# Control-Board-V3-Charging_v21.net
KiCad netlist of a schematic drawn in EAGLE
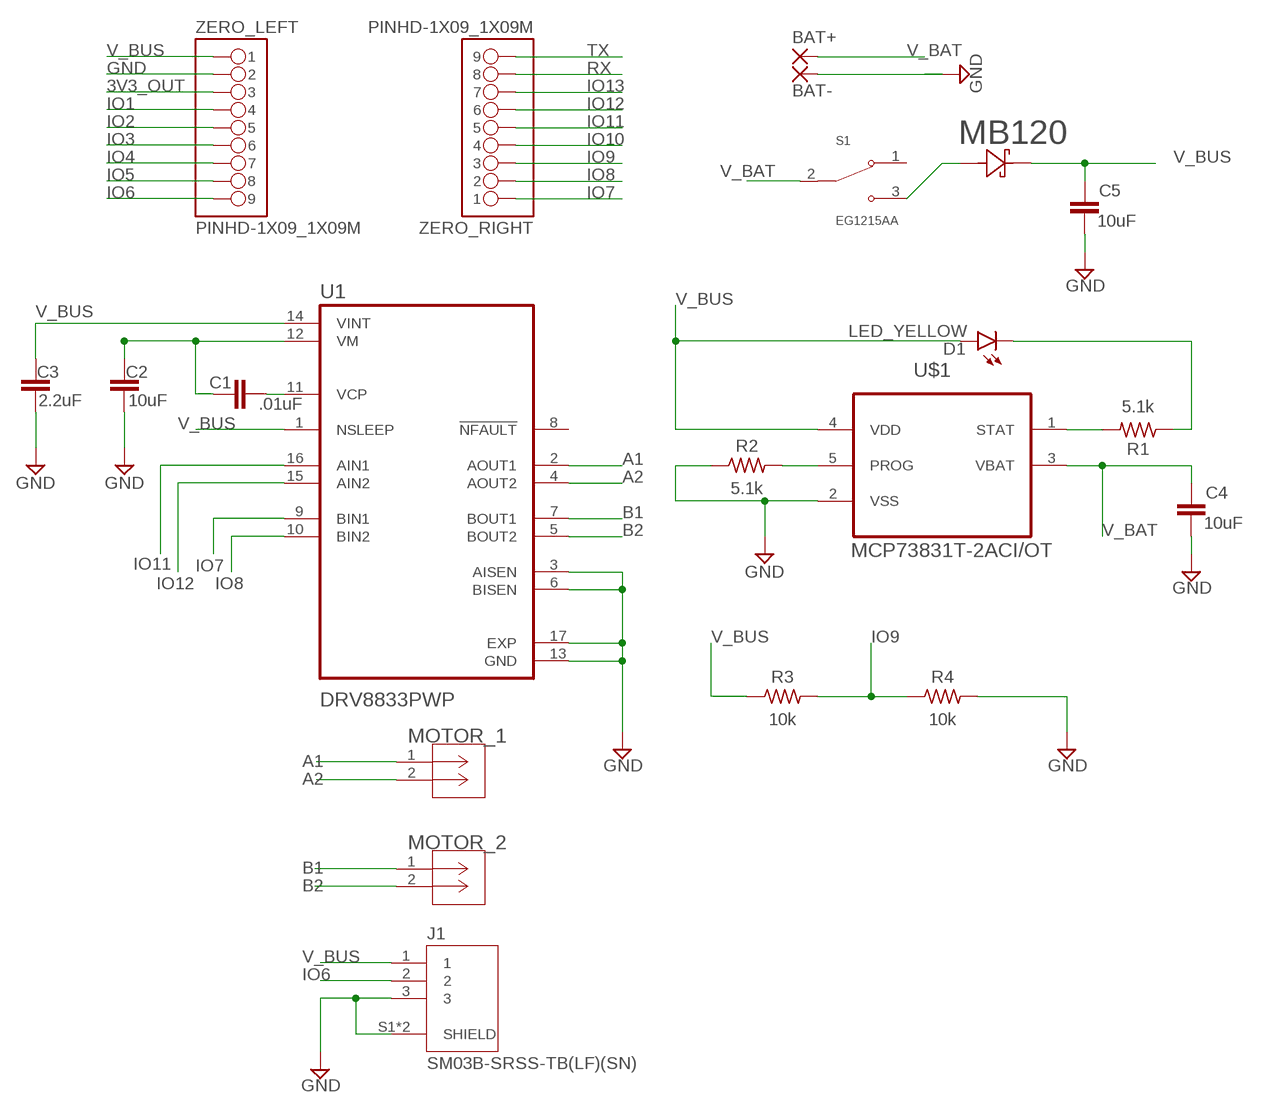
[diagram p0: schematic, sheet 1]

(export (version "E")
  (design (tool "Eeschema 10.0.6"))
  (components
    (comp (ref "BAT+")
      (value "SMD2")
      (footprint "eagle-import:SMD1,27-2,54")
      (libsource (lib "eagle-import") (part "SMD2"))
    )
    (comp (ref "BAT-")
      (value "SMD2")
      (footprint "eagle-import:SMD1,27-2,54")
      (libsource (lib "eagle-import") (part "SMD2"))
    )
    (comp (ref "C1")
      (value ".01uF")
      (footprint "eagle-import:CAPC2012X110")
      (libsource (lib "eagle-import") (part "CCHIP-0805(2012-METRIC)_"))
    )
    (comp (ref "C2")
      (value "10uF")
      (footprint "eagle-import:CAPC2012X110")
      (libsource (lib "eagle-import") (part "CCHIP-0805(2012-METRIC)_"))
    )
    (comp (ref "C3")
      (value "2.2uF")
      (footprint "eagle-import:CAPC2012X110")
      (libsource (lib "eagle-import") (part "CCHIP-0805(2012-METRIC)_"))
    )
    (comp (ref "C4")
      (value "10uF")
      (footprint "eagle-import:CAPC2012X110")
      (libsource (lib "eagle-import") (part "Capacitor_16290819_CCHIP-0805(2012-METRIC)_"))
    )
    (comp (ref "C5")
      (value "10uF")
      (footprint "eagle-import:CAPC2012X110")
      (libsource (lib "eagle-import") (part "Capacitor_16290819_CCHIP-0805(2012-METRIC)_"))
    )
    (comp (ref "D1")
      (value "LED_YELLOW")
      (footprint "eagle-import:LEDC2012X110N_FLAT-Y")
      (libsource (lib "eagle-import") (part "CHIP-FLAT-Y_0805"))
    )
    (comp (ref "J1")
      (value "SM03B-SRSS-TB(LF)(SN)")
      (footprint "eagle-import:JST_SM03B-SRSS-TB(LF)(SN)")
      (fields (field (name "MF") "JST Sales America Inc."))
      (libsource (lib "eagle-import") (part "SM03B-SRSS-TB(LF)(SN)"))
    )
    (comp (ref "MB120")
      (value "MBR120LSFT3GSDO_SOD-123FL(498)_OSI-L")
      (footprint "eagle-import:SDO_SOD-123FL(498)_OSI-L")
      (fields
        (field (name "MANUFACTURER_PART_NUMBER") "MBR120LSFT3G")
        (field (name "COPYRIGHT") "Copyright (C) 2024 Ultra Librarian. All rights reserved.")
      )
      (libsource (lib "eagle-import") (part "MBR120LSFT3GSDO_SOD-123FL(498)_OSI-L"))
    )
    (comp (ref "MOTOR_1")
      (value "JST_SH")
      (footprint "eagle-import:JST")
      (libsource (lib "eagle-import") (part "JST_SH"))
    )
    (comp (ref "MOTOR_2")
      (value "JST_SH")
      (footprint "eagle-import:JST")
      (libsource (lib "eagle-import") (part "JST_SH"))
    )
    (comp (ref "R1")
      (value "5.1k")
      (footprint "eagle-import:RESC2012X65")
      (libsource (lib "eagle-import") (part "R-USCHIP-0805(2012-METRIC)_"))
    )
    (comp (ref "R2")
      (value "5.1k")
      (footprint "eagle-import:RESC2012X65")
      (libsource (lib "eagle-import") (part "R-USCHIP-0805(2012-METRIC)_"))
    )
    (comp (ref "R3")
      (value "10k")
      (footprint "eagle-import:RESC2012X65")
      (libsource (lib "eagle-import") (part "R-USCHIP-0805(2012-METRIC)_"))
    )
    (comp (ref "R4")
      (value "10k")
      (footprint "eagle-import:RESC2012X65")
      (libsource (lib "eagle-import") (part "R-USCHIP-0805(2012-METRIC)_"))
    )
    (comp (ref "S1")
      (value "EG1215AA")
      (footprint "eagle-import:SW_EG1215AA")
      (fields (field (name "MANUFACTURER") "E Switch"))
      (libsource (lib "eagle-import") (part "EG1215AA"))
    )
    (comp (ref "U$1")
      (value "MCP73831T-2ACI/OT")
      (footprint "eagle-import:SOT95P280X145-5N")
      (libsource (lib "eagle-import") (part "MCP73831T-2ACI/OT"))
    )
    (comp (ref "U1")
      (value "DRV8833PWP")
      (footprint "eagle-import:IC_DRV8833PWP")
      (fields (field (name "MANUFACTURER") "Texas Instruments"))
      (libsource (lib "eagle-import") (part "DRV8833PWP"))
    )
    (comp (ref "ZERO_LEFT")
      (value "PINHD-1X09_1X09M")
      (footprint "eagle-import:1X09")
      (libsource (lib "eagle-import") (part "PINHD-1X09_1X09M"))
    )
    (comp (ref "ZERO_RIGHT")
      (value "PINHD-1X09_1X09M")
      (footprint "eagle-import:1X09")
      (libsource (lib "eagle-import") (part "PINHD-1X09_1X09M"))
    )
  )
  (nets
    (net (code "1") (name "/3V3_OUT") (class "Default")
      (node (ref "ZERO_LEFT") (pin "3") (pinfunction "3_3") (pintype "bidirectional"))
    )
    (net (code "2") (name "/A1") (class "Default")
      (node (ref "MOTOR_1") (pin "1") (pinfunction "1_1") (pintype "passive"))
      (node (ref "U1") (pin "2") (pinfunction "AOUT1_2") (pintype "output"))
    )
    (net (code "3") (name "/A2") (class "Default")
      (node (ref "MOTOR_1") (pin "2") (pinfunction "2_2") (pintype "passive"))
      (node (ref "U1") (pin "4") (pinfunction "AOUT2_4") (pintype "output"))
    )
    (net (code "4") (name "/B1") (class "Default")
      (node (ref "MOTOR_2") (pin "1") (pinfunction "1_1") (pintype "passive"))
      (node (ref "U1") (pin "7") (pinfunction "BOUT1_7") (pintype "output"))
    )
    (net (code "5") (name "/B2") (class "Default")
      (node (ref "MOTOR_2") (pin "2") (pinfunction "2_2") (pintype "passive"))
      (node (ref "U1") (pin "5") (pinfunction "BOUT2_5") (pintype "output"))
    )
    (net (code "6") (name "/IO1") (class "Default")
      (node (ref "ZERO_LEFT") (pin "4") (pinfunction "4_4") (pintype "bidirectional"))
    )
    (net (code "7") (name "/IO2") (class "Default")
      (node (ref "ZERO_LEFT") (pin "5") (pinfunction "5_5") (pintype "bidirectional"))
    )
    (net (code "8") (name "/IO3") (class "Default")
      (node (ref "ZERO_LEFT") (pin "6") (pinfunction "6_6") (pintype "bidirectional"))
    )
    (net (code "9") (name "/IO4") (class "Default")
      (node (ref "ZERO_LEFT") (pin "7") (pinfunction "7_7") (pintype "bidirectional"))
    )
    (net (code "10") (name "/IO5") (class "Default")
      (node (ref "ZERO_LEFT") (pin "8") (pinfunction "8_8") (pintype "bidirectional"))
    )
    (net (code "11") (name "/IO6") (class "Default")
      (node (ref "J1") (pin "2") (pinfunction "2_2") (pintype "passive"))
      (node (ref "ZERO_LEFT") (pin "9") (pinfunction "9_9") (pintype "bidirectional"))
    )
    (net (code "12") (name "/IO7") (class "Default")
      (node (ref "U1") (pin "9") (pinfunction "BIN1_9") (pintype "input"))
      (node (ref "ZERO_RIGHT") (pin "1") (pinfunction "1_1") (pintype "bidirectional"))
    )
    (net (code "13") (name "/IO8") (class "Default")
      (node (ref "U1") (pin "10") (pinfunction "BIN2_10") (pintype "input"))
      (node (ref "ZERO_RIGHT") (pin "2") (pinfunction "2_2") (pintype "bidirectional"))
    )
    (net (code "14") (name "/IO9") (class "Default")
      (node (ref "R3") (pin "2") (pinfunction "2_2") (pintype "passive"))
      (node (ref "R4") (pin "1") (pinfunction "1_1") (pintype "passive"))
      (node (ref "ZERO_RIGHT") (pin "3") (pinfunction "3_3") (pintype "bidirectional"))
    )
    (net (code "15") (name "/IO10") (class "Default")
      (node (ref "ZERO_RIGHT") (pin "4") (pinfunction "4_4") (pintype "bidirectional"))
    )
    (net (code "16") (name "/IO11") (class "Default")
      (node (ref "U1") (pin "16") (pinfunction "AIN1_16") (pintype "input"))
      (node (ref "ZERO_RIGHT") (pin "5") (pinfunction "5_5") (pintype "bidirectional"))
    )
    (net (code "17") (name "/IO12") (class "Default")
      (node (ref "U1") (pin "15") (pinfunction "AIN2_15") (pintype "input"))
      (node (ref "ZERO_RIGHT") (pin "6") (pinfunction "6_6") (pintype "bidirectional"))
    )
    (net (code "18") (name "/IO13") (class "Default")
      (node (ref "ZERO_RIGHT") (pin "7") (pinfunction "7_7") (pintype "bidirectional"))
    )
    (net (code "19") (name "/RX") (class "Default")
      (node (ref "ZERO_RIGHT") (pin "8") (pinfunction "8_8") (pintype "bidirectional"))
    )
    (net (code "20") (name "/TX") (class "Default")
      (node (ref "ZERO_RIGHT") (pin "9") (pinfunction "9_9") (pintype "bidirectional"))
    )
    (net (code "21") (name "/V_BAT") (class "Default")
      (node (ref "BAT+") (pin "1") (pinfunction "P_1") (pintype "passive"))
      (node (ref "C4") (pin "1") (pinfunction "1_1") (pintype "passive"))
      (node (ref "S1") (pin "2") (pinfunction "2_2") (pintype "passive"))
      (node (ref "U$1") (pin "3") (pinfunction "VBAT_3") (pintype "output"))
    )
    (net (code "22") (name "/V_BUS") (class "Default")
      (node (ref "C1") (pin "1") (pinfunction "1_1") (pintype "passive"))
      (node (ref "C2") (pin "2") (pinfunction "2_2") (pintype "passive"))
      (node (ref "C3") (pin "2") (pinfunction "2_2") (pintype "passive"))
      (node (ref "C5") (pin "1") (pinfunction "1_1") (pintype "passive"))
      (node (ref "D1") (pin "A") (pinfunction "A_A") (pintype "passive"))
      (node (ref "J1") (pin "1") (pinfunction "1_1") (pintype "passive"))
      (node (ref "MB120") (pin "1") (pinfunction "1_1") (pintype "passive"))
      (node (ref "R3") (pin "1") (pinfunction "1_1") (pintype "passive"))
      (node (ref "U$1") (pin "4") (pinfunction "VDD_4") (pintype "power_in"))
      (node (ref "U1") (pin "1") (pinfunction "NSLEEP_1") (pintype "input"))
      (node (ref "U1") (pin "12") (pinfunction "VM_12") (pintype "power_in"))
      (node (ref "U1") (pin "14") (pinfunction "VINT_14") (pintype "power_in"))
      (node (ref "ZERO_LEFT") (pin "1") (pinfunction "1_1") (pintype "bidirectional"))
    )
    (net (code "23") (name "GND") (class "Default")
      (node (ref "BAT-") (pin "1") (pinfunction "P_1") (pintype "passive"))
      (node (ref "C2") (pin "1") (pinfunction "1_1") (pintype "passive"))
      (node (ref "C3") (pin "1") (pinfunction "1_1") (pintype "passive"))
      (node (ref "C4") (pin "2") (pinfunction "2_2") (pintype "passive"))
      (node (ref "C5") (pin "2") (pinfunction "2_2") (pintype "passive"))
      (node (ref "J1") (pin "3") (pinfunction "3_3") (pintype "passive"))
      (node (ref "J1") (pin "S1") (pinfunction "SHIELD_S1") (pintype "passive"))
      (node (ref "J1") (pin "S2") (pinfunction "SHIELD_S2") (pintype "passive"))
      (node (ref "R2") (pin "1") (pinfunction "1_1") (pintype "passive"))
      (node (ref "R4") (pin "2") (pinfunction "2_2") (pintype "passive"))
      (node (ref "U$1") (pin "2") (pinfunction "VSS_2") (pintype "power_in"))
      (node (ref "U1") (pin "13") (pinfunction "GND_13") (pintype "power_in"))
      (node (ref "U1") (pin "17") (pinfunction "EXP_17") (pintype "passive"))
      (node (ref "U1") (pin "3") (pinfunction "AISEN_3") (pintype "bidirectional"))
      (node (ref "U1") (pin "6") (pinfunction "BISEN_6") (pintype "bidirectional"))
      (node (ref "ZERO_LEFT") (pin "2") (pinfunction "2_2") (pintype "bidirectional"))
    )
    (net (code "24") (name "Net-(D1-PadC)") (class "Default")
      (node (ref "D1") (pin "C") (pinfunction "C_C") (pintype "passive"))
      (node (ref "R1") (pin "1") (pinfunction "1_1") (pintype "passive"))
    )
    (net (code "25") (name "Net-(MB120-Pad2)") (class "Default")
      (node (ref "MB120") (pin "2") (pinfunction "2_2") (pintype "passive"))
      (node (ref "S1") (pin "3") (pinfunction "3_3") (pintype "passive"))
    )
    (net (code "26") (name "Net-(U$1-PROG)") (class "Default")
      (node (ref "R2") (pin "2") (pinfunction "2_2") (pintype "passive"))
      (node (ref "U$1") (pin "5") (pinfunction "PROG_5") (pintype "input"))
    )
    (net (code "27") (name "Net-(U$1-STAT)") (class "Default")
      (node (ref "R1") (pin "2") (pinfunction "2_2") (pintype "passive"))
      (node (ref "U$1") (pin "1") (pinfunction "STAT_1") (pintype "output"))
    )
    (net (code "28") (name "Net-(U1-VCP)") (class "Default")
      (node (ref "C1") (pin "2") (pinfunction "2_2") (pintype "passive"))
      (node (ref "U1") (pin "11") (pinfunction "VCP_11") (pintype "bidirectional"))
    )
    (net (code "29") (name "unconnected-(S1-Pad1)") (class "Default")
      (node (ref "S1") (pin "1") (pinfunction "1_1") (pintype "passive"))
    )
    (net (code "30") (name "unconnected-(U1-~{NFAULT}-Pad8)") (class "Default")
      (node (ref "U1") (pin "8") (pinfunction "~{NFAULT}_8") (pintype "output"))
    )
  )
)
